# Analog.net
KiCad netlist of a schematic drawn in Altium Designer
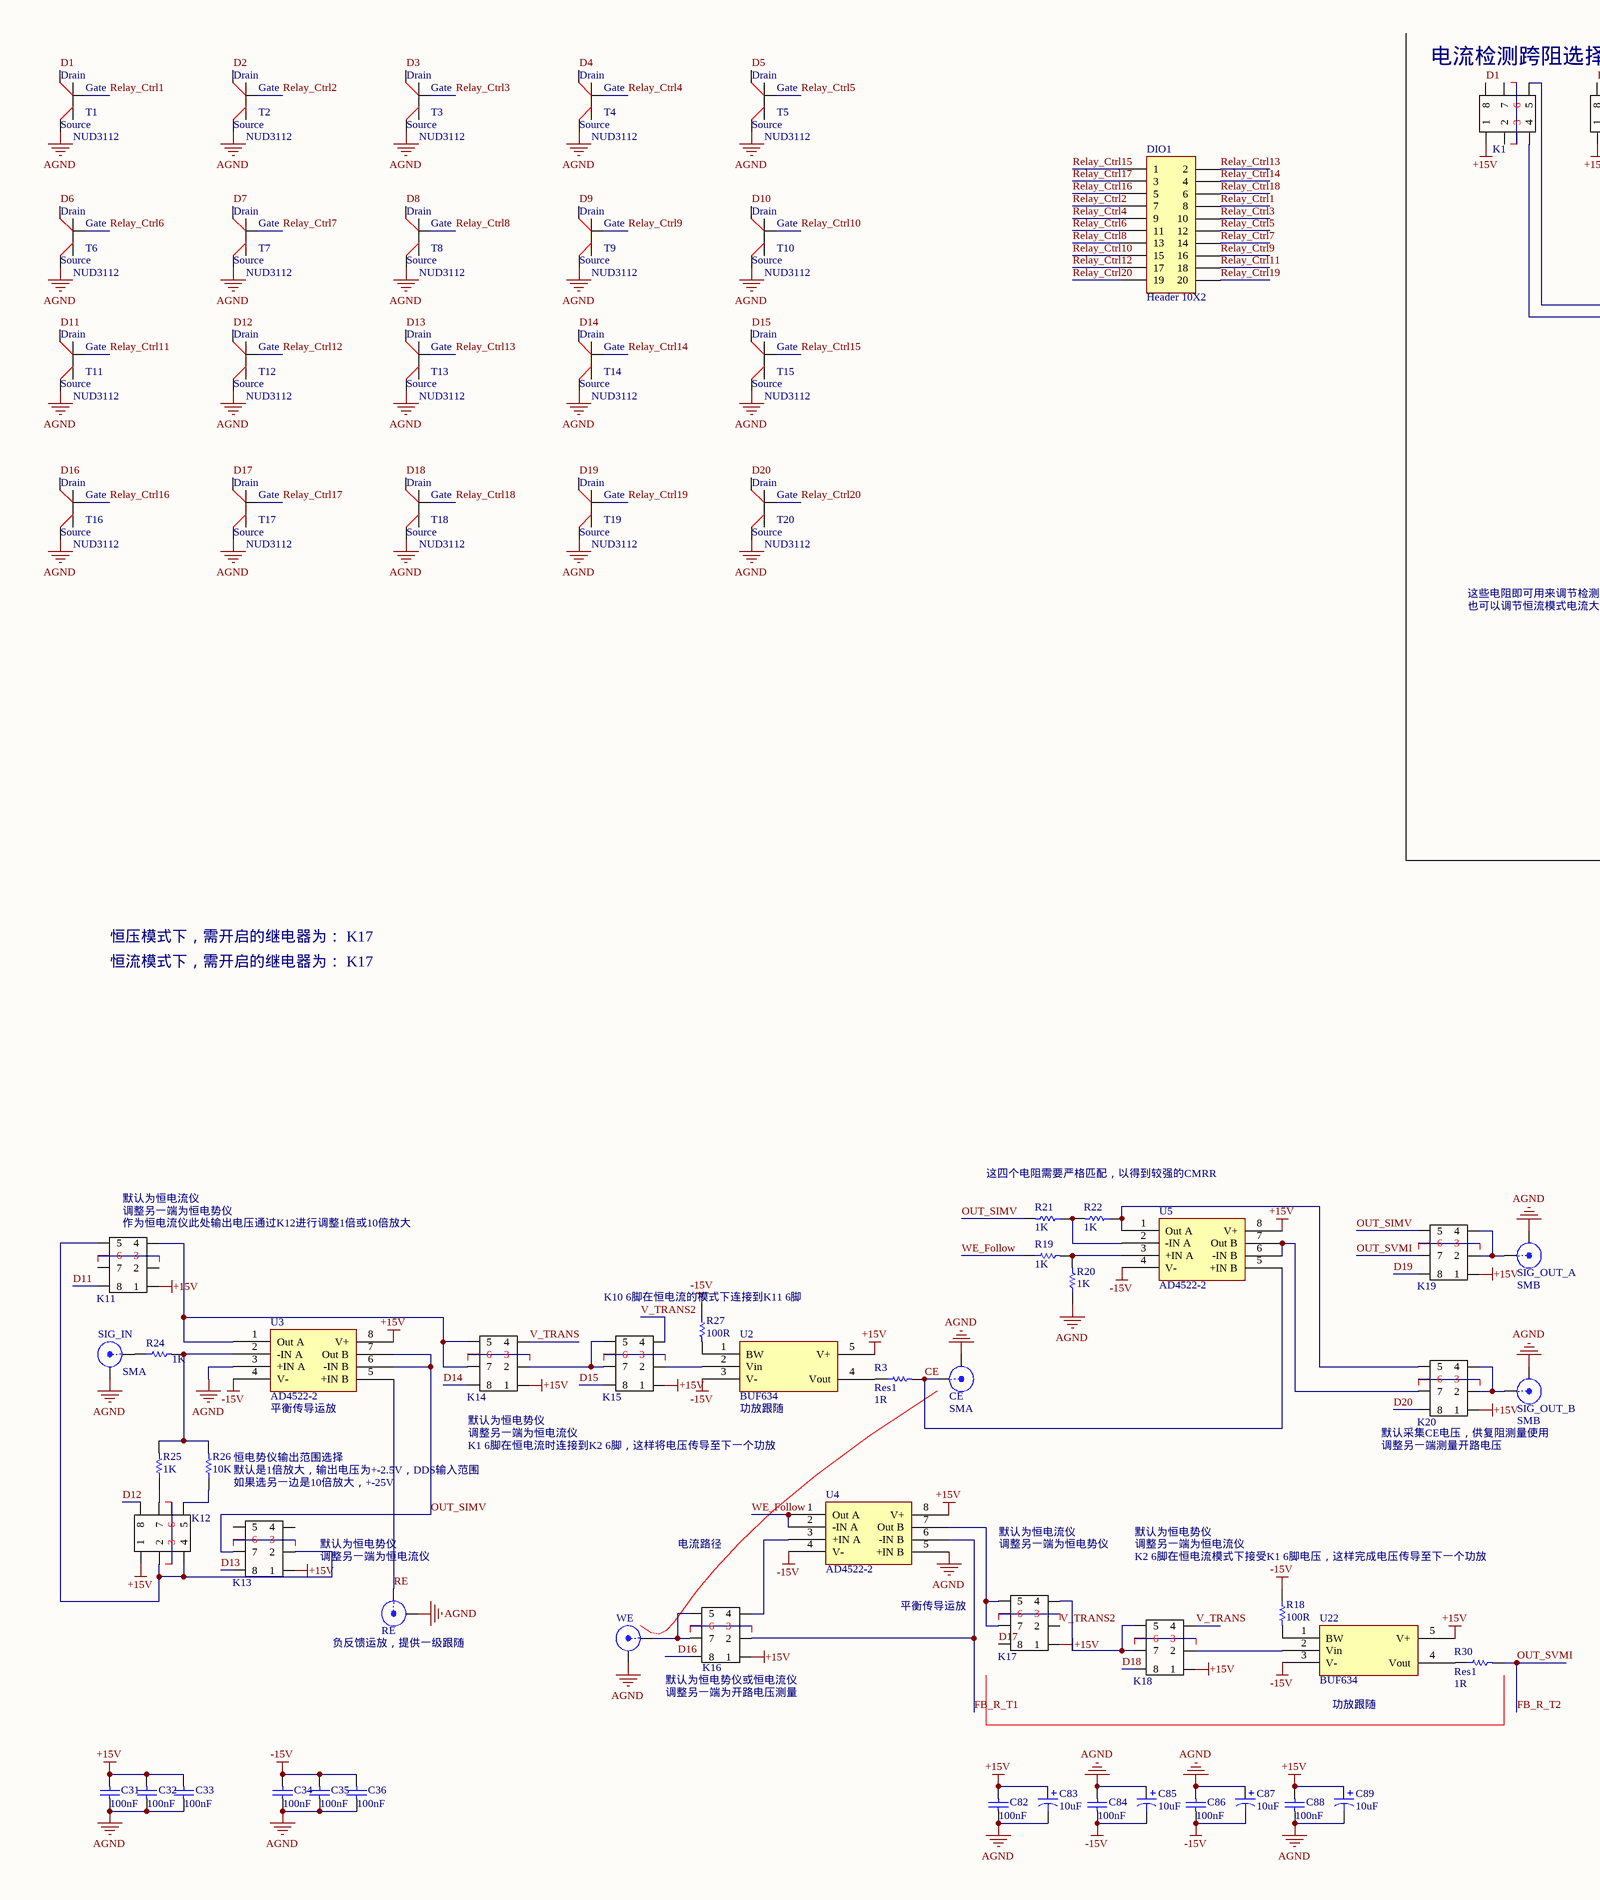
[diagram p0: Analog.SchDoc, left]
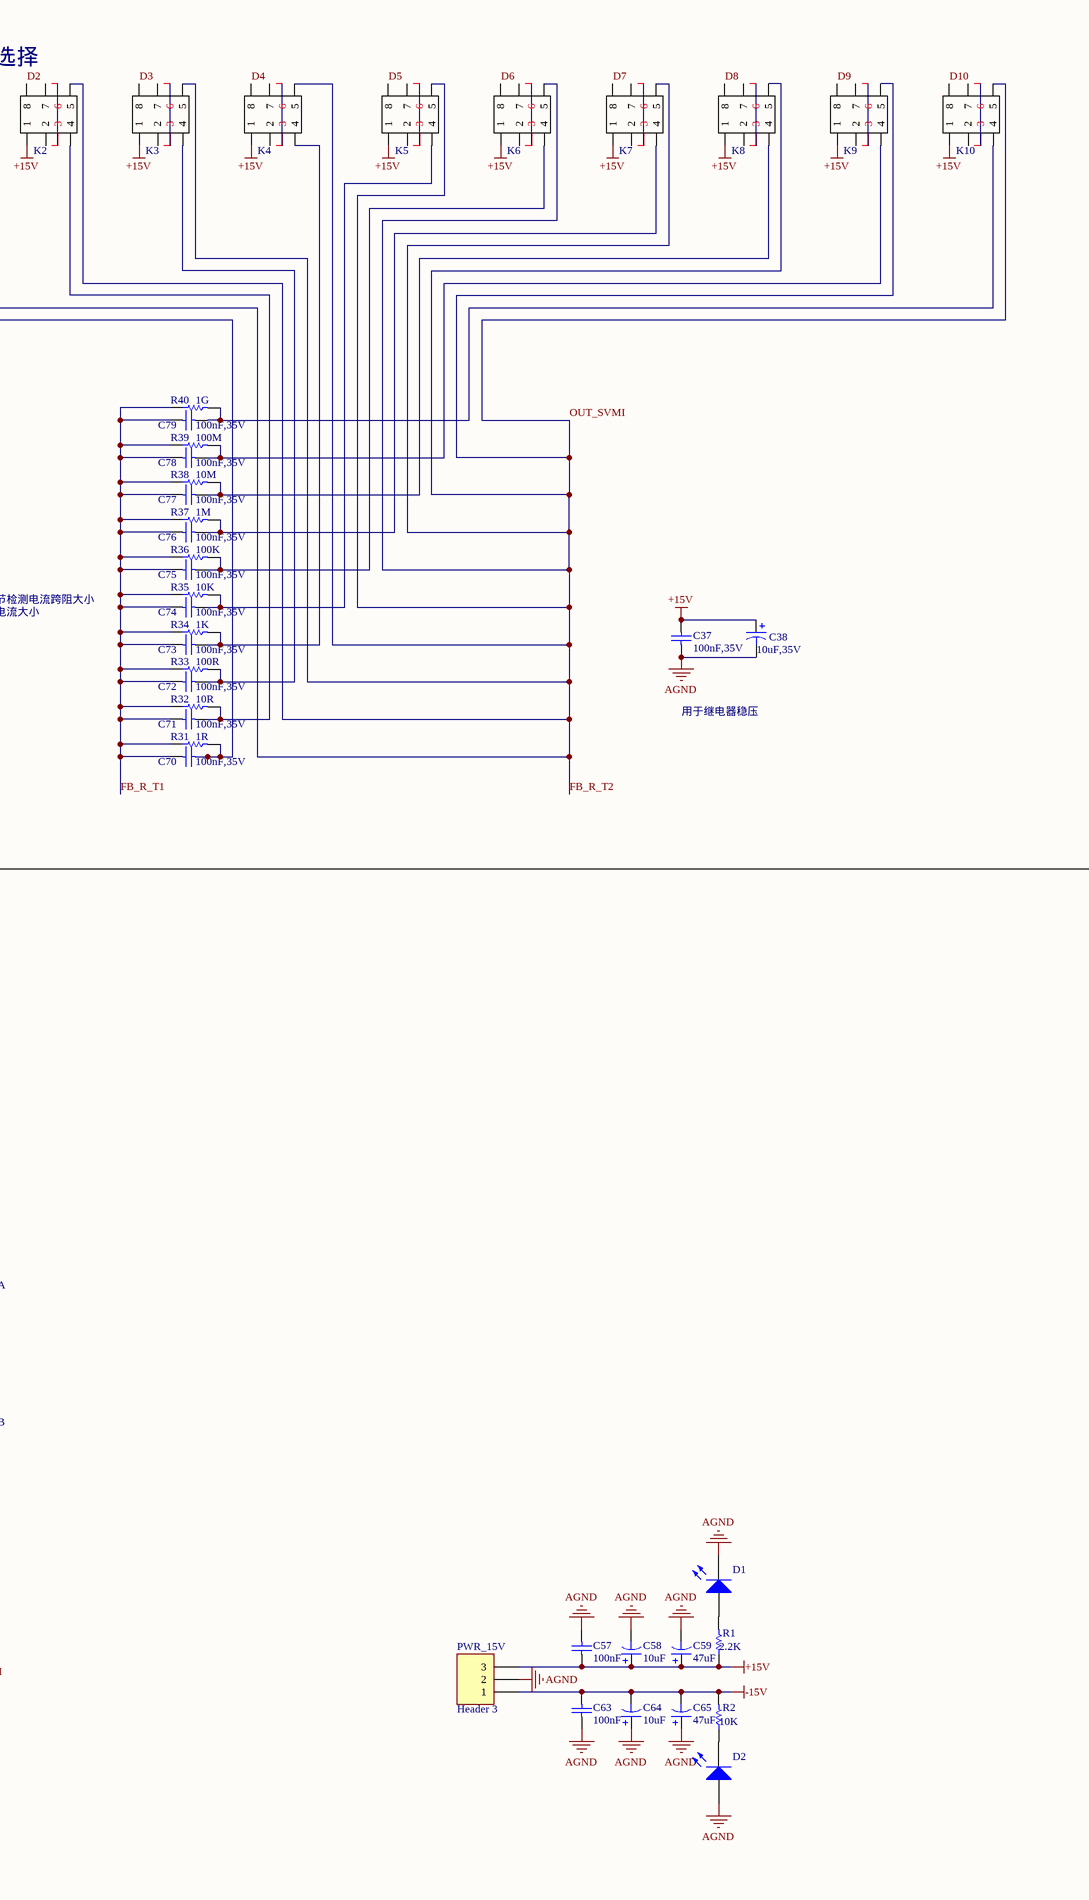
[diagram p1: Analog.SchDoc, right]

(export (version "E")
  (design (tool "Eeschema 10.0.6"))
  (components
    (comp (ref "C31")
      (value "100nF")
      (footprint "0805")
      (description "Capacitor")
      (fields (field (name "PUBLISHER") "Altium Limited"))
      (libsource (lib "Miscellaneous Devices") (part "Cap"))
    )
    (comp (ref "C32")
      (value "100nF")
      (footprint "0805")
      (description "Capacitor")
      (fields (field (name "PUBLISHER") "Altium Limited"))
      (libsource (lib "Miscellaneous Devices") (part "Cap"))
    )
    (comp (ref "C33")
      (value "100nF")
      (footprint "0805")
      (description "Capacitor")
      (fields (field (name "PUBLISHER") "Altium Limited"))
      (libsource (lib "Miscellaneous Devices") (part "Cap"))
    )
    (comp (ref "C34")
      (value "100nF")
      (footprint "0805")
      (description "Capacitor")
      (fields (field (name "PUBLISHER") "Altium Limited"))
      (libsource (lib "Miscellaneous Devices") (part "Cap"))
    )
    (comp (ref "C35")
      (value "100nF")
      (footprint "0805")
      (description "Capacitor")
      (fields (field (name "PUBLISHER") "Altium Limited"))
      (libsource (lib "Miscellaneous Devices") (part "Cap"))
    )
    (comp (ref "C36")
      (value "100nF")
      (footprint "0805")
      (description "Capacitor")
      (fields (field (name "PUBLISHER") "Altium Limited"))
      (libsource (lib "Miscellaneous Devices") (part "Cap"))
    )
    (comp (ref "C37")
      (value "100nF,35V")
      (footprint "0805")
      (description "Capacitor")
      (fields (field (name "Comment") "Cap") (field (name "PUBLISHER") "Altium Limited"))
      (libsource (lib "Miscellaneous Devices") (part "Cap"))
    )
    (comp (ref "C38")
      (value "10uF,35V")
      (footprint "6032_pol")
      (description "Polarized Capacitor (Radial)")
      (fields (field (name "Comment") "Cap Pol1") (field (name "PUBLISHER") "Altium Limited"))
      (libsource (lib "Miscellaneous Devices") (part "Cap Pol1"))
    )
    (comp (ref "C57")
      (value "100nF")
      (footprint "0805")
      (description "Capacitor,100V")
      (fields (field (name "PUBLISHER") "Altium Limited"))
      (libsource (lib "Miscellaneous Devices") (part "Cap"))
    )
    (comp (ref "C58")
      (value "10uF")
      (footprint "6032_pol")
      (description "Polarized Capacitor (Radial)")
      (fields (field (name "Comment") "10uF,50V") (field (name "PUBLISHER") "Altium Limited"))
      (libsource (lib "Miscellaneous Devices") (part "Cap Pol1"))
    )
    (comp (ref "C59")
      (value "47uF")
      (footprint "cap_pol_8*10.2")
      (description "Polarized Capacitor (Radial)")
      (fields (field (name "Comment") "47uF,50V") (field (name "PUBLISHER") "Altium Limited"))
      (libsource (lib "Miscellaneous Devices") (part "Cap Pol1"))
    )
    (comp (ref "C63")
      (value "100nF")
      (footprint "0805")
      (description "Capacitor,100V")
      (fields (field (name "PUBLISHER") "Altium Limited"))
      (libsource (lib "Miscellaneous Devices") (part "Cap"))
    )
    (comp (ref "C64")
      (value "10uF")
      (footprint "6032_pol")
      (description "Polarized Capacitor (Radial)")
      (fields (field (name "Comment") "10uF,50V") (field (name "PUBLISHER") "Altium Limited"))
      (libsource (lib "Miscellaneous Devices") (part "Cap Pol1"))
    )
    (comp (ref "C65")
      (value "47uF")
      (footprint "cap_pol_8*10.2")
      (description "Polarized Capacitor (Radial)")
      (fields (field (name "Comment") "47uF,50V") (field (name "PUBLISHER") "Altium Limited"))
      (libsource (lib "Miscellaneous Devices") (part "Cap Pol1"))
    )
    (comp (ref "C70")
      (value "100nF,35V")
      (footprint "0805")
      (description "Capacitor")
      (fields (field (name "Comment") "Cap") (field (name "PUBLISHER") "Altium Limited"))
      (libsource (lib "Miscellaneous Devices") (part "Cap"))
    )
    (comp (ref "C71")
      (value "100nF,35V")
      (footprint "0805")
      (description "Capacitor")
      (fields (field (name "Comment") "Cap") (field (name "PUBLISHER") "Altium Limited"))
      (libsource (lib "Miscellaneous Devices") (part "Cap"))
    )
    (comp (ref "C72")
      (value "100nF,35V")
      (footprint "0805")
      (description "Capacitor")
      (fields (field (name "Comment") "Cap") (field (name "PUBLISHER") "Altium Limited"))
      (libsource (lib "Miscellaneous Devices") (part "Cap"))
    )
    (comp (ref "C73")
      (value "100nF,35V")
      (footprint "0805")
      (description "Capacitor")
      (fields (field (name "Comment") "Cap") (field (name "PUBLISHER") "Altium Limited"))
      (libsource (lib "Miscellaneous Devices") (part "Cap"))
    )
    (comp (ref "C74")
      (value "100nF,35V")
      (footprint "0805")
      (description "Capacitor")
      (fields (field (name "Comment") "Cap") (field (name "PUBLISHER") "Altium Limited"))
      (libsource (lib "Miscellaneous Devices") (part "Cap"))
    )
    (comp (ref "C75")
      (value "100nF,35V")
      (footprint "0805")
      (description "Capacitor")
      (fields (field (name "Comment") "Cap") (field (name "PUBLISHER") "Altium Limited"))
      (libsource (lib "Miscellaneous Devices") (part "Cap"))
    )
    (comp (ref "C76")
      (value "100nF,35V")
      (footprint "0805")
      (description "Capacitor")
      (fields (field (name "Comment") "Cap") (field (name "PUBLISHER") "Altium Limited"))
      (libsource (lib "Miscellaneous Devices") (part "Cap"))
    )
    (comp (ref "C77")
      (value "100nF,35V")
      (footprint "0805")
      (description "Capacitor")
      (fields (field (name "Comment") "Cap") (field (name "PUBLISHER") "Altium Limited"))
      (libsource (lib "Miscellaneous Devices") (part "Cap"))
    )
    (comp (ref "C78")
      (value "100nF,35V")
      (footprint "0805")
      (description "Capacitor")
      (fields (field (name "Comment") "Cap") (field (name "PUBLISHER") "Altium Limited"))
      (libsource (lib "Miscellaneous Devices") (part "Cap"))
    )
    (comp (ref "C79")
      (value "100nF,35V")
      (footprint "0805")
      (description "Capacitor")
      (fields (field (name "Comment") "Cap") (field (name "PUBLISHER") "Altium Limited"))
      (libsource (lib "Miscellaneous Devices") (part "Cap"))
    )
    (comp (ref "C82")
      (value "100nF")
      (footprint "0805")
      (description "Capacitor")
      (fields (field (name "PUBLISHER") "Altium Limited"))
      (libsource (lib "Miscellaneous Devices") (part "Cap"))
    )
    (comp (ref "C83")
      (value "10uF")
      (footprint "6032_pol")
      (description "Polarized Capacitor (Radial)")
      (fields (field (name "PUBLISHER") "Altium Limited"))
      (libsource (lib "Miscellaneous Devices") (part "Cap Pol1"))
    )
    (comp (ref "C84")
      (value "100nF")
      (footprint "0805")
      (description "Capacitor")
      (fields (field (name "PUBLISHER") "Altium Limited"))
      (libsource (lib "Miscellaneous Devices") (part "Cap"))
    )
    (comp (ref "C85")
      (value "10uF")
      (footprint "6032_pol")
      (description "Polarized Capacitor (Radial)")
      (fields (field (name "PUBLISHER") "Altium Limited"))
      (libsource (lib "Miscellaneous Devices") (part "Cap Pol1"))
    )
    (comp (ref "C86")
      (value "100nF")
      (footprint "0805")
      (description "Capacitor")
      (fields (field (name "PUBLISHER") "Altium Limited"))
      (libsource (lib "Miscellaneous Devices") (part "Cap"))
    )
    (comp (ref "C87")
      (value "10uF")
      (footprint "6032_pol")
      (description "Polarized Capacitor (Radial)")
      (fields (field (name "PUBLISHER") "Altium Limited"))
      (libsource (lib "Miscellaneous Devices") (part "Cap Pol1"))
    )
    (comp (ref "C88")
      (value "100nF")
      (footprint "0805")
      (description "Capacitor")
      (fields (field (name "PUBLISHER") "Altium Limited"))
      (libsource (lib "Miscellaneous Devices") (part "Cap"))
    )
    (comp (ref "C89")
      (value "10uF")
      (footprint "6032_pol")
      (description "Polarized Capacitor (Radial)")
      (fields (field (name "PUBLISHER") "Altium Limited"))
      (libsource (lib "Miscellaneous Devices") (part "Cap Pol1"))
    )
    (comp (ref "CE")
      (value "SMA")
      (footprint "SMA_SMT")
      (description "SMB Straight Connector")
      (fields (field (name "PUBLISHER") "Altium Limited"))
      (libsource (lib "Miscellaneous Connectors") (part "SMB"))
    )
    (comp (ref "D1")
      (value "LED3")
      (footprint "0805_pol1")
      (description "Typical BLUE SiC LED")
      (fields (field (name "PUBLISHER") "Altium Limited"))
      (libsource (lib "Miscellaneous Devices") (part "LED3"))
    )
    (comp (ref "D2")
      (value "LED3")
      (footprint "0805_pol1")
      (description "Typical BLUE SiC LED")
      (fields (field (name "PUBLISHER") "Altium Limited"))
      (libsource (lib "Miscellaneous Devices") (part "LED3"))
    )
    (comp (ref "DIO1")
      (value "Header 10X2")
      (footprint "HDR2X10")
      (description "Header, 10-Pin, Dual row")
      (fields (field (name "PUBLISHER") "Altium Limited"))
      (libsource (lib "Miscellaneous Connectors") (part "Header 10X2"))
    )
    (comp (ref "K1")
      (value "AXICOM IM")
      (footprint "AXICOM_IM06")
      (libsource (lib "BinFeng_IC") (part "AXiCOM IM05"))
    )
    (comp (ref "K2")
      (value "AXICOM IM")
      (footprint "AXICOM_IM06")
      (libsource (lib "BinFeng_IC") (part "AXiCOM IM05"))
    )
    (comp (ref "K3")
      (value "AXICOM IM")
      (footprint "AXICOM_IM06")
      (libsource (lib "BinFeng_IC") (part "AXiCOM IM05"))
    )
    (comp (ref "K4")
      (value "AXICOM IM")
      (footprint "AXICOM_IM06")
      (libsource (lib "BinFeng_IC") (part "AXiCOM IM05"))
    )
    (comp (ref "K5")
      (value "AXICOM IM")
      (footprint "AXICOM_IM06")
      (libsource (lib "BinFeng_IC") (part "AXiCOM IM05"))
    )
    (comp (ref "K6")
      (value "AXICOM IM")
      (footprint "AXICOM_IM06")
      (libsource (lib "BinFeng_IC") (part "AXiCOM IM05"))
    )
    (comp (ref "K7")
      (value "AXICOM IM")
      (footprint "AXICOM_IM06")
      (libsource (lib "BinFeng_IC") (part "AXiCOM IM05"))
    )
    (comp (ref "K8")
      (value "AXICOM IM")
      (footprint "AXICOM_IM06")
      (libsource (lib "BinFeng_IC") (part "AXiCOM IM05"))
    )
    (comp (ref "K9")
      (value "AXICOM IM")
      (footprint "AXICOM_IM06")
      (libsource (lib "BinFeng_IC") (part "AXiCOM IM05"))
    )
    (comp (ref "K10")
      (value "AXICOM IM")
      (footprint "AXICOM_IM06")
      (libsource (lib "BinFeng_IC") (part "AXiCOM IM05"))
    )
    (comp (ref "K11")
      (value "AXICOM IM")
      (footprint "AXICOM_IM06")
      (libsource (lib "BinFeng_IC") (part "AXiCOM IM05"))
    )
    (comp (ref "K12")
      (value "AXICOM IM")
      (footprint "AXICOM_IM06")
      (libsource (lib "BinFeng_IC") (part "AXiCOM IM05"))
    )
    (comp (ref "K13")
      (value "AXICOM IM")
      (footprint "AXICOM_IM06")
      (libsource (lib "BinFeng_IC") (part "AXiCOM IM05"))
    )
    (comp (ref "K14")
      (value "AXICOM IM")
      (footprint "AXICOM_IM06")
      (libsource (lib "BinFeng_IC") (part "AXiCOM IM05"))
    )
    (comp (ref "K15")
      (value "AXICOM IM")
      (footprint "AXICOM_IM06")
      (libsource (lib "BinFeng_IC") (part "AXiCOM IM05"))
    )
    (comp (ref "K16")
      (value "AXICOM IM")
      (footprint "AXICOM_IM06")
      (libsource (lib "BinFeng_IC") (part "AXiCOM IM05"))
    )
    (comp (ref "K17")
      (value "AXICOM IM")
      (footprint "AXICOM_IM06")
      (libsource (lib "BinFeng_IC") (part "AXiCOM IM05"))
    )
    (comp (ref "K18")
      (value "AXICOM IM")
      (footprint "AXICOM_IM06")
      (libsource (lib "BinFeng_IC") (part "AXiCOM IM05"))
    )
    (comp (ref "K19")
      (value "AXICOM IM")
      (footprint "AXICOM_IM06")
      (libsource (lib "BinFeng_IC") (part "AXiCOM IM05"))
    )
    (comp (ref "K20")
      (value "AXICOM IM")
      (footprint "AXICOM_IM06")
      (libsource (lib "BinFeng_IC") (part "AXiCOM IM05"))
    )
    (comp (ref "PWR_15V")
      (value "Header 3")
      (footprint "PWR_3T")
      (description "Header, 3-Pin")
      (fields (field (name "PUBLISHER") "Altium Limited"))
      (libsource (lib "Miscellaneous Connectors") (part "Header 3"))
    )
    (comp (ref "R1")
      (value "2.2K")
      (footprint "BinFeng:0603")
      (description "Resistor")
      (fields (field (name "Comment") "10K") (field (name "PUBLISHER") "Altium Limited"))
      (libsource (lib "Miscellaneous Devices") (part "Res1"))
    )
    (comp (ref "R2")
      (value "10K")
      (footprint "BinFeng:0603")
      (description "Resistor")
      (fields (field (name "Comment") "2.2K") (field (name "PUBLISHER") "Altium Limited"))
      (libsource (lib "Miscellaneous Devices") (part "Res1"))
    )
    (comp (ref "R3")
      (value "Res1")
      (footprint "1206")
      (description "Resistor")
      (fields (field (name "ALTIUM_VALUE") "1R") (field (name "PUBLISHER") "Altium Limited"))
      (libsource (lib "Miscellaneous Devices") (part "Res1"))
    )
    (comp (ref "R18")
      (value "100R")
      (footprint "0805")
      (description "Resistor")
      (fields (field (name "Comment") "Res1") (field (name "PUBLISHER") "Altium Limited"))
      (libsource (lib "Miscellaneous Devices") (part "Res1"))
    )
    (comp (ref "R19")
      (value "1K")
      (footprint "0805")
      (description "Resistor")
      (fields (field (name "Comment") "Res1") (field (name "PUBLISHER") "Altium Limited"))
      (libsource (lib "Miscellaneous Devices") (part "Res1"))
    )
    (comp (ref "R20")
      (value "1K")
      (footprint "0805")
      (description "Resistor")
      (fields (field (name "Comment") "Res1") (field (name "PUBLISHER") "Altium Limited"))
      (libsource (lib "Miscellaneous Devices") (part "Res1"))
    )
    (comp (ref "R21")
      (value "1K")
      (footprint "0805")
      (description "Resistor")
      (fields (field (name "Comment") "Res1") (field (name "PUBLISHER") "Altium Limited"))
      (libsource (lib "Miscellaneous Devices") (part "Res1"))
    )
    (comp (ref "R22")
      (value "1K")
      (footprint "0805")
      (description "Resistor")
      (fields (field (name "Comment") "Res1") (field (name "PUBLISHER") "Altium Limited"))
      (libsource (lib "Miscellaneous Devices") (part "Res1"))
    )
    (comp (ref "R24")
      (value "1K")
      (footprint "0805")
      (description "Resistor")
      (fields (field (name "Comment") "Res1") (field (name "PUBLISHER") "Altium Limited"))
      (libsource (lib "Miscellaneous Devices") (part "Res1"))
    )
    (comp (ref "R25")
      (value "1K")
      (footprint "0805")
      (description "Resistor")
      (fields (field (name "Comment") "Res1") (field (name "PUBLISHER") "Altium Limited"))
      (libsource (lib "Miscellaneous Devices") (part "Res1"))
    )
    (comp (ref "R26")
      (value "10K")
      (footprint "0805")
      (description "Resistor")
      (fields (field (name "Comment") "Res1") (field (name "PUBLISHER") "Altium Limited"))
      (libsource (lib "Miscellaneous Devices") (part "Res1"))
    )
    (comp (ref "R27")
      (value "100R")
      (footprint "0805")
      (description "Resistor")
      (fields (field (name "Comment") "Res1") (field (name "PUBLISHER") "Altium Limited"))
      (libsource (lib "Miscellaneous Devices") (part "Res1"))
    )
    (comp (ref "R30")
      (value "Res1")
      (footprint "1206")
      (description "Resistor")
      (fields (field (name "ALTIUM_VALUE") "1R") (field (name "PUBLISHER") "Altium Limited"))
      (libsource (lib "Miscellaneous Devices") (part "Res1"))
    )
    (comp (ref "R31")
      (value "1R")
      (footprint "0805")
      (description "Resistor")
      (fields (field (name "Comment") "Res1") (field (name "PUBLISHER") "Altium Limited"))
      (libsource (lib "Miscellaneous Devices") (part "Res1"))
    )
    (comp (ref "R32")
      (value "10R")
      (footprint "0805")
      (description "Resistor")
      (fields (field (name "Comment") "Res1") (field (name "PUBLISHER") "Altium Limited"))
      (libsource (lib "Miscellaneous Devices") (part "Res1"))
    )
    (comp (ref "R33")
      (value "100R")
      (footprint "0805")
      (description "Resistor")
      (fields (field (name "Comment") "Res1") (field (name "PUBLISHER") "Altium Limited"))
      (libsource (lib "Miscellaneous Devices") (part "Res1"))
    )
    (comp (ref "R34")
      (value "1K")
      (footprint "0805")
      (description "Resistor")
      (fields (field (name "Comment") "Res1") (field (name "PUBLISHER") "Altium Limited"))
      (libsource (lib "Miscellaneous Devices") (part "Res1"))
    )
    (comp (ref "R35")
      (value "10K")
      (footprint "0805")
      (description "Resistor")
      (fields (field (name "Comment") "Res1") (field (name "PUBLISHER") "Altium Limited"))
      (libsource (lib "Miscellaneous Devices") (part "Res1"))
    )
    (comp (ref "R36")
      (value "100K")
      (footprint "0805")
      (description "Resistor")
      (fields (field (name "Comment") "Res1") (field (name "PUBLISHER") "Altium Limited"))
      (libsource (lib "Miscellaneous Devices") (part "Res1"))
    )
    (comp (ref "R37")
      (value "1M")
      (footprint "0805")
      (description "Resistor")
      (fields (field (name "Comment") "Res1") (field (name "PUBLISHER") "Altium Limited"))
      (libsource (lib "Miscellaneous Devices") (part "Res1"))
    )
    (comp (ref "R38")
      (value "10M")
      (footprint "0805")
      (description "Resistor")
      (fields (field (name "Comment") "Res1") (field (name "PUBLISHER") "Altium Limited"))
      (libsource (lib "Miscellaneous Devices") (part "Res1"))
    )
    (comp (ref "R39")
      (value "100M")
      (footprint "0805")
      (description "Resistor")
      (fields (field (name "Comment") "Res1") (field (name "PUBLISHER") "Altium Limited"))
      (libsource (lib "Miscellaneous Devices") (part "Res1"))
    )
    (comp (ref "R40")
      (value "1G")
      (footprint "0805")
      (description "Resistor")
      (fields (field (name "Comment") "Res1") (field (name "PUBLISHER") "Altium Limited"))
      (libsource (lib "Miscellaneous Devices") (part "Res1"))
    )
    (comp (ref "RE")
      (value "SMB")
      (footprint "SMA_SMT")
      (description "SMB Straight Connector")
      (fields (field (name "PUBLISHER") "Altium Limited"))
      (libsource (lib "Miscellaneous Connectors") (part "SMB"))
    )
    (comp (ref "SIG_IN")
      (value "SMA")
      (footprint "SMA_SMT")
      (description "SMB Straight Connector")
      (fields (field (name "PUBLISHER") "Altium Limited"))
      (libsource (lib "Miscellaneous Connectors") (part "SMB"))
    )
    (comp (ref "SIG_OUT_A")
      (value "SMB")
      (footprint "SMA_SMT")
      (description "SMB Straight Connector")
      (fields (field (name "PUBLISHER") "Altium Limited"))
      (libsource (lib "Miscellaneous Connectors") (part "SMB"))
    )
    (comp (ref "SIG_OUT_B")
      (value "SMB")
      (footprint "SMA_SMT")
      (description "SMB Straight Connector")
      (fields (field (name "PUBLISHER") "Altium Limited"))
      (libsource (lib "Miscellaneous Connectors") (part "SMB"))
    )
    (comp (ref "T1")
      (value "NUD3112")
      (footprint "SOT-23")
      (description "Relay Driver 5V Supply")
      (libsource (lib "BinFeng_IC") (part "NUD3105"))
    )
    (comp (ref "T2")
      (value "NUD3112")
      (footprint "SOT-23")
      (description "Relay Driver 5V Supply")
      (libsource (lib "BinFeng_IC") (part "NUD3105"))
    )
    (comp (ref "T3")
      (value "NUD3112")
      (footprint "SOT-23")
      (description "Relay Driver 5V Supply")
      (libsource (lib "BinFeng_IC") (part "NUD3105"))
    )
    (comp (ref "T4")
      (value "NUD3112")
      (footprint "SOT-23")
      (description "Relay Driver 5V Supply")
      (libsource (lib "BinFeng_IC") (part "NUD3105"))
    )
    (comp (ref "T5")
      (value "NUD3112")
      (footprint "SOT-23")
      (description "Relay Driver 5V Supply")
      (libsource (lib "BinFeng_IC") (part "NUD3105"))
    )
    (comp (ref "T6")
      (value "NUD3112")
      (footprint "SOT-23")
      (description "Relay Driver 5V Supply")
      (libsource (lib "BinFeng_IC") (part "NUD3105"))
    )
    (comp (ref "T7")
      (value "NUD3112")
      (footprint "SOT-23")
      (description "Relay Driver 5V Supply")
      (libsource (lib "BinFeng_IC") (part "NUD3105"))
    )
    (comp (ref "T8")
      (value "NUD3112")
      (footprint "SOT-23")
      (description "Relay Driver 5V Supply")
      (libsource (lib "BinFeng_IC") (part "NUD3105"))
    )
    (comp (ref "T9")
      (value "NUD3112")
      (footprint "SOT-23")
      (description "Relay Driver 5V Supply")
      (libsource (lib "BinFeng_IC") (part "NUD3105"))
    )
    (comp (ref "T10")
      (value "NUD3112")
      (footprint "SOT-23")
      (description "Relay Driver 5V Supply")
      (libsource (lib "BinFeng_IC") (part "NUD3105"))
    )
    (comp (ref "T11")
      (value "NUD3112")
      (footprint "SOT-23")
      (description "Relay Driver 5V Supply")
      (libsource (lib "BinFeng_IC") (part "NUD3105"))
    )
    (comp (ref "T12")
      (value "NUD3112")
      (footprint "SOT-23")
      (description "Relay Driver 5V Supply")
      (libsource (lib "BinFeng_IC") (part "NUD3105"))
    )
    (comp (ref "T13")
      (value "NUD3112")
      (footprint "SOT-23")
      (description "Relay Driver 5V Supply")
      (libsource (lib "BinFeng_IC") (part "NUD3105"))
    )
    (comp (ref "T14")
      (value "NUD3112")
      (footprint "SOT-23")
      (description "Relay Driver 5V Supply")
      (libsource (lib "BinFeng_IC") (part "NUD3105"))
    )
    (comp (ref "T15")
      (value "NUD3112")
      (footprint "SOT-23")
      (description "Relay Driver 5V Supply")
      (libsource (lib "BinFeng_IC") (part "NUD3105"))
    )
    (comp (ref "T16")
      (value "NUD3112")
      (footprint "SOT-23")
      (description "Relay Driver 5V Supply")
      (libsource (lib "BinFeng_IC") (part "NUD3105"))
    )
    (comp (ref "T17")
      (value "NUD3112")
      (footprint "SOT-23")
      (description "Relay Driver 5V Supply")
      (libsource (lib "BinFeng_IC") (part "NUD3105"))
    )
    (comp (ref "T18")
      (value "NUD3112")
      (footprint "SOT-23")
      (description "Relay Driver 5V Supply")
      (libsource (lib "BinFeng_IC") (part "NUD3105"))
    )
    (comp (ref "T19")
      (value "NUD3112")
      (footprint "SOT-23")
      (description "Relay Driver 5V Supply")
      (libsource (lib "BinFeng_IC") (part "NUD3105"))
    )
    (comp (ref "T20")
      (value "NUD3112")
      (footprint "SOT-23")
      (description "Relay Driver 5V Supply")
      (libsource (lib "BinFeng_IC") (part "NUD3105"))
    )
    (comp (ref "U2") (value "BUF634") (footprint "PSFM-T5") (libsource (lib "BinFeng_IC") (part "BUF634")))
    (comp (ref "U3") (value "AD4522-2") (footprint "SO-8N") (libsource (lib "BinFeng_IC") (part "AD8676")))
    (comp (ref "U4") (value "AD4522-2") (footprint "SO-8N") (libsource (lib "BinFeng_IC") (part "AD8676")))
    (comp (ref "U5") (value "AD4522-2") (footprint "SO-8N") (libsource (lib "BinFeng_IC") (part "AD8676")))
    (comp (ref "U22") (value "BUF634") (footprint "PSFM-T5") (libsource (lib "BinFeng_IC") (part "BUF634")))
    (comp (ref "WE")
      (value "SMB")
      (footprint "SMA_SMT")
      (description "SMB Straight Connector")
      (fields (field (name "PUBLISHER") "Altium Limited"))
      (libsource (lib "Miscellaneous Connectors") (part "SMB"))
    )
  )
  (nets
    (net (code "1") (name "+15V") (class "Default")
      (node (ref "C31") (pin "2") (pinfunction "2_2") (pintype "passive"))
      (node (ref "C32") (pin "2") (pinfunction "2_2") (pintype "passive"))
      (node (ref "C33") (pin "2") (pinfunction "2_2") (pintype "passive"))
      (node (ref "C37") (pin "2") (pinfunction "2_2") (pintype "passive"))
      (node (ref "C38") (pin "1") (pinfunction "1_1") (pintype "passive"))
      (node (ref "C57") (pin "2") (pinfunction "2_2") (pintype "passive"))
      (node (ref "C58") (pin "1") (pinfunction "1_1") (pintype "passive"))
      (node (ref "C59") (pin "1") (pinfunction "1_1") (pintype "passive"))
      (node (ref "C82") (pin "2") (pinfunction "2_2") (pintype "passive"))
      (node (ref "C83") (pin "1") (pinfunction "1_1") (pintype "passive"))
      (node (ref "C88") (pin "2") (pinfunction "2_2") (pintype "passive"))
      (node (ref "C89") (pin "1") (pinfunction "1_1") (pintype "passive"))
      (node (ref "K1") (pin "1") (pinfunction "1_1") (pintype "passive"))
      (node (ref "K10") (pin "1") (pinfunction "1_1") (pintype "passive"))
      (node (ref "K11") (pin "1") (pinfunction "1_1") (pintype "passive"))
      (node (ref "K12") (pin "1") (pinfunction "1_1") (pintype "passive"))
      (node (ref "K13") (pin "1") (pinfunction "1_1") (pintype "passive"))
      (node (ref "K14") (pin "1") (pinfunction "1_1") (pintype "passive"))
      (node (ref "K15") (pin "1") (pinfunction "1_1") (pintype "passive"))
      (node (ref "K16") (pin "1") (pinfunction "1_1") (pintype "passive"))
      (node (ref "K17") (pin "1") (pinfunction "1_1") (pintype "passive"))
      (node (ref "K18") (pin "1") (pinfunction "1_1") (pintype "passive"))
      (node (ref "K19") (pin "1") (pinfunction "1_1") (pintype "passive"))
      (node (ref "K2") (pin "1") (pinfunction "1_1") (pintype "passive"))
      (node (ref "K20") (pin "1") (pinfunction "1_1") (pintype "passive"))
      (node (ref "K3") (pin "1") (pinfunction "1_1") (pintype "passive"))
      (node (ref "K4") (pin "1") (pinfunction "1_1") (pintype "passive"))
      (node (ref "K5") (pin "1") (pinfunction "1_1") (pintype "passive"))
      (node (ref "K6") (pin "1") (pinfunction "1_1") (pintype "passive"))
      (node (ref "K7") (pin "1") (pinfunction "1_1") (pintype "passive"))
      (node (ref "K8") (pin "1") (pinfunction "1_1") (pintype "passive"))
      (node (ref "K9") (pin "1") (pinfunction "1_1") (pintype "passive"))
      (node (ref "PWR_15V") (pin "3") (pinfunction "3_3") (pintype "passive"))
      (node (ref "R1") (pin "1") (pinfunction "1_1") (pintype "passive"))
      (node (ref "U2") (pin "5") (pinfunction "V+_5") (pintype "passive"))
      (node (ref "U22") (pin "5") (pinfunction "V+_5") (pintype "passive"))
      (node (ref "U3") (pin "8") (pinfunction "V+_8") (pintype "passive"))
      (node (ref "U4") (pin "8") (pinfunction "V+_8") (pintype "passive"))
      (node (ref "U5") (pin "8") (pinfunction "V+_8") (pintype "passive"))
    )
    (net (code "2") (name "-15V") (class "Default")
      (node (ref "C34") (pin "2") (pinfunction "2_2") (pintype "passive"))
      (node (ref "C35") (pin "2") (pinfunction "2_2") (pintype "passive"))
      (node (ref "C36") (pin "2") (pinfunction "2_2") (pintype "passive"))
      (node (ref "C63") (pin "1") (pinfunction "1_1") (pintype "passive"))
      (node (ref "C64") (pin "2") (pinfunction "2_2") (pintype "passive"))
      (node (ref "C65") (pin "2") (pinfunction "2_2") (pintype "passive"))
      (node (ref "C84") (pin "1") (pinfunction "1_1") (pintype "passive"))
      (node (ref "C85") (pin "2") (pinfunction "2_2") (pintype "passive"))
      (node (ref "C86") (pin "1") (pinfunction "1_1") (pintype "passive"))
      (node (ref "C87") (pin "2") (pinfunction "2_2") (pintype "passive"))
      (node (ref "PWR_15V") (pin "1") (pinfunction "1_1") (pintype "passive"))
      (node (ref "R18") (pin "1") (pinfunction "1_1") (pintype "passive"))
      (node (ref "R2") (pin "2") (pinfunction "2_2") (pintype "passive"))
      (node (ref "R27") (pin "1") (pinfunction "1_1") (pintype "passive"))
      (node (ref "U2") (pin "3") (pinfunction "V-_3") (pintype "passive"))
      (node (ref "U22") (pin "3") (pinfunction "V-_3") (pintype "passive"))
      (node (ref "U3") (pin "4") (pinfunction "V-_4") (pintype "passive"))
      (node (ref "U4") (pin "4") (pinfunction "V-_4") (pintype "passive"))
      (node (ref "U5") (pin "4") (pinfunction "V-_4") (pintype "passive"))
    )
    (net (code "3") (name "/CE") (class "Default")
      (node (ref "CE") (pin "1") (pinfunction "X_1") (pintype "passive"))
      (node (ref "R3") (pin "2") (pinfunction "2_2") (pintype "passive"))
      (node (ref "U5") (pin "5") (pinfunction "+IN_B_5") (pintype "passive"))
    )
    (net (code "4") (name "/D1") (class "Default")
      (node (ref "K1") (pin "8") (pinfunction "8_8") (pintype "passive"))
      (node (ref "T1") (pin "3") (pinfunction "Drain_3") (pintype "passive"))
    )
    (net (code "5") (name "/D2") (class "Default")
      (node (ref "K2") (pin "8") (pinfunction "8_8") (pintype "passive"))
      (node (ref "T2") (pin "3") (pinfunction "Drain_3") (pintype "passive"))
    )
    (net (code "6") (name "/D3") (class "Default")
      (node (ref "K3") (pin "8") (pinfunction "8_8") (pintype "passive"))
      (node (ref "T3") (pin "3") (pinfunction "Drain_3") (pintype "passive"))
    )
    (net (code "7") (name "/D4") (class "Default")
      (node (ref "K4") (pin "8") (pinfunction "8_8") (pintype "passive"))
      (node (ref "T4") (pin "3") (pinfunction "Drain_3") (pintype "passive"))
    )
    (net (code "8") (name "/D5") (class "Default")
      (node (ref "K5") (pin "8") (pinfunction "8_8") (pintype "passive"))
      (node (ref "T5") (pin "3") (pinfunction "Drain_3") (pintype "passive"))
    )
    (net (code "9") (name "/D6") (class "Default")
      (node (ref "K6") (pin "8") (pinfunction "8_8") (pintype "passive"))
      (node (ref "T6") (pin "3") (pinfunction "Drain_3") (pintype "passive"))
    )
    (net (code "10") (name "/D7") (class "Default")
      (node (ref "K7") (pin "8") (pinfunction "8_8") (pintype "passive"))
      (node (ref "T7") (pin "3") (pinfunction "Drain_3") (pintype "passive"))
    )
    (net (code "11") (name "/D8") (class "Default")
      (node (ref "K8") (pin "8") (pinfunction "8_8") (pintype "passive"))
      (node (ref "T8") (pin "3") (pinfunction "Drain_3") (pintype "passive"))
    )
    (net (code "12") (name "/D9") (class "Default")
      (node (ref "K9") (pin "8") (pinfunction "8_8") (pintype "passive"))
      (node (ref "T9") (pin "3") (pinfunction "Drain_3") (pintype "passive"))
    )
    (net (code "13") (name "/D10") (class "Default")
      (node (ref "K10") (pin "8") (pinfunction "8_8") (pintype "passive"))
      (node (ref "T10") (pin "3") (pinfunction "Drain_3") (pintype "passive"))
    )
    (net (code "14") (name "/D11") (class "Default")
      (node (ref "K11") (pin "8") (pinfunction "8_8") (pintype "passive"))
      (node (ref "T11") (pin "3") (pinfunction "Drain_3") (pintype "passive"))
    )
    (net (code "15") (name "/D12") (class "Default")
      (node (ref "K12") (pin "8") (pinfunction "8_8") (pintype "passive"))
      (node (ref "T12") (pin "3") (pinfunction "Drain_3") (pintype "passive"))
    )
    (net (code "16") (name "/D13") (class "Default")
      (node (ref "K13") (pin "8") (pinfunction "8_8") (pintype "passive"))
      (node (ref "T13") (pin "3") (pinfunction "Drain_3") (pintype "passive"))
    )
    (net (code "17") (name "/D14") (class "Default")
      (node (ref "K14") (pin "8") (pinfunction "8_8") (pintype "passive"))
      (node (ref "T14") (pin "3") (pinfunction "Drain_3") (pintype "passive"))
    )
    (net (code "18") (name "/D15") (class "Default")
      (node (ref "K15") (pin "8") (pinfunction "8_8") (pintype "passive"))
      (node (ref "T15") (pin "3") (pinfunction "Drain_3") (pintype "passive"))
    )
    (net (code "19") (name "/D16") (class "Default")
      (node (ref "K16") (pin "8") (pinfunction "8_8") (pintype "passive"))
      (node (ref "T16") (pin "3") (pinfunction "Drain_3") (pintype "passive"))
    )
    (net (code "20") (name "/D17") (class "Default")
      (node (ref "K17") (pin "8") (pinfunction "8_8") (pintype "passive"))
      (node (ref "T17") (pin "3") (pinfunction "Drain_3") (pintype "passive"))
    )
    (net (code "21") (name "/D18") (class "Default")
      (node (ref "K18") (pin "8") (pinfunction "8_8") (pintype "passive"))
      (node (ref "T18") (pin "3") (pinfunction "Drain_3") (pintype "passive"))
    )
    (net (code "22") (name "/D19") (class "Default")
      (node (ref "K19") (pin "8") (pinfunction "8_8") (pintype "passive"))
      (node (ref "T19") (pin "3") (pinfunction "Drain_3") (pintype "passive"))
    )
    (net (code "23") (name "/D20") (class "Default")
      (node (ref "K20") (pin "8") (pinfunction "8_8") (pintype "passive"))
      (node (ref "T20") (pin "3") (pinfunction "Drain_3") (pintype "passive"))
    )
    (net (code "24") (name "/FB_R_T1") (class "Default")
      (node (ref "C70") (pin "1") (pinfunction "1_1") (pintype "passive"))
      (node (ref "C71") (pin "1") (pinfunction "1_1") (pintype "passive"))
      (node (ref "C72") (pin "1") (pinfunction "1_1") (pintype "passive"))
      (node (ref "C73") (pin "1") (pinfunction "1_1") (pintype "passive"))
      (node (ref "C74") (pin "1") (pinfunction "1_1") (pintype "passive"))
      (node (ref "C75") (pin "1") (pinfunction "1_1") (pintype "passive"))
      (node (ref "C76") (pin "1") (pinfunction "1_1") (pintype "passive"))
      (node (ref "C77") (pin "1") (pinfunction "1_1") (pintype "passive"))
      (node (ref "C78") (pin "1") (pinfunction "1_1") (pintype "passive"))
      (node (ref "C79") (pin "1") (pinfunction "1_1") (pintype "passive"))
      (node (ref "K16") (pin "2") (pinfunction "2_2") (pintype "passive"))
      (node (ref "R31") (pin "1") (pinfunction "1_1") (pintype "passive"))
      (node (ref "R32") (pin "1") (pinfunction "1_1") (pintype "passive"))
      (node (ref "R33") (pin "1") (pinfunction "1_1") (pintype "passive"))
      (node (ref "R34") (pin "1") (pinfunction "1_1") (pintype "passive"))
      (node (ref "R35") (pin "1") (pinfunction "1_1") (pintype "passive"))
      (node (ref "R36") (pin "1") (pinfunction "1_1") (pintype "passive"))
      (node (ref "R37") (pin "1") (pinfunction "1_1") (pintype "passive"))
      (node (ref "R38") (pin "1") (pinfunction "1_1") (pintype "passive"))
      (node (ref "R39") (pin "1") (pinfunction "1_1") (pintype "passive"))
      (node (ref "R40") (pin "1") (pinfunction "1_1") (pintype "passive"))
      (node (ref "U4") (pin "6") (pinfunction "-IN_B_6") (pintype "passive"))
    )
    (net (code "25") (name "/FB_R_T2") (class "Default")
      (node (ref "K1") (pin "5") (pinfunction "5_5") (pintype "passive"))
      (node (ref "K10") (pin "5") (pinfunction "5_5") (pintype "passive"))
      (node (ref "K19") (pin "7") (pinfunction "7_7") (pintype "passive"))
      (node (ref "K2") (pin "5") (pinfunction "5_5") (pintype "passive"))
      (node (ref "K3") (pin "5") (pinfunction "5_5") (pintype "passive"))
      (node (ref "K4") (pin "5") (pinfunction "5_5") (pintype "passive"))
      (node (ref "K5") (pin "5") (pinfunction "5_5") (pintype "passive"))
      (node (ref "K6") (pin "5") (pinfunction "5_5") (pintype "passive"))
      (node (ref "K7") (pin "5") (pinfunction "5_5") (pintype "passive"))
      (node (ref "K8") (pin "5") (pinfunction "5_5") (pintype "passive"))
      (node (ref "K9") (pin "5") (pinfunction "5_5") (pintype "passive"))
      (node (ref "R30") (pin "2") (pinfunction "2_2") (pintype "passive"))
    )
    (net (code "26") (name "/OUT_SIMV") (class "Default")
      (node (ref "K13") (pin "7") (pinfunction "7_7") (pintype "passive"))
      (node (ref "K19") (pin "5") (pinfunction "5_5") (pintype "passive"))
      (node (ref "R21") (pin "2") (pinfunction "2_2") (pintype "passive"))
      (node (ref "U3") (pin "6") (pinfunction "-IN_B_6") (pintype "passive"))
      (node (ref "U3") (pin "7") (pinfunction "Out_B_7") (pintype "passive"))
    )
    (net (code "27") (name "/RE") (class "Default")
      (node (ref "RE") (pin "1") (pinfunction "X_1") (pintype "passive"))
      (node (ref "U3") (pin "5") (pinfunction "+IN_B_5") (pintype "passive"))
    )
    (net (code "28") (name "/Relay_Ctrl1") (class "Default")
      (node (ref "DIO1") (pin "8") (pinfunction "8_8") (pintype "passive"))
      (node (ref "T1") (pin "1") (pinfunction "Gate_1") (pintype "passive"))
    )
    (net (code "29") (name "/Relay_Ctrl2") (class "Default")
      (node (ref "DIO1") (pin "7") (pinfunction "7_7") (pintype "passive"))
      (node (ref "T2") (pin "1") (pinfunction "Gate_1") (pintype "passive"))
    )
    (net (code "30") (name "/Relay_Ctrl3") (class "Default")
      (node (ref "DIO1") (pin "10") (pinfunction "10_10") (pintype "passive"))
      (node (ref "T3") (pin "1") (pinfunction "Gate_1") (pintype "passive"))
    )
    (net (code "31") (name "/Relay_Ctrl4") (class "Default")
      (node (ref "DIO1") (pin "9") (pinfunction "9_9") (pintype "passive"))
      (node (ref "T4") (pin "1") (pinfunction "Gate_1") (pintype "passive"))
    )
    (net (code "32") (name "/Relay_Ctrl5") (class "Default")
      (node (ref "DIO1") (pin "12") (pinfunction "12_12") (pintype "passive"))
      (node (ref "T5") (pin "1") (pinfunction "Gate_1") (pintype "passive"))
    )
    (net (code "33") (name "/Relay_Ctrl6") (class "Default")
      (node (ref "DIO1") (pin "11") (pinfunction "11_11") (pintype "passive"))
      (node (ref "T6") (pin "1") (pinfunction "Gate_1") (pintype "passive"))
    )
    (net (code "34") (name "/Relay_Ctrl7") (class "Default")
      (node (ref "DIO1") (pin "14") (pinfunction "14_14") (pintype "passive"))
      (node (ref "T7") (pin "1") (pinfunction "Gate_1") (pintype "passive"))
    )
    (net (code "35") (name "/Relay_Ctrl8") (class "Default")
      (node (ref "DIO1") (pin "13") (pinfunction "13_13") (pintype "passive"))
      (node (ref "T8") (pin "1") (pinfunction "Gate_1") (pintype "passive"))
    )
    (net (code "36") (name "/Relay_Ctrl9") (class "Default")
      (node (ref "DIO1") (pin "16") (pinfunction "16_16") (pintype "passive"))
      (node (ref "T9") (pin "1") (pinfunction "Gate_1") (pintype "passive"))
    )
    (net (code "37") (name "/Relay_Ctrl10") (class "Default")
      (node (ref "DIO1") (pin "15") (pinfunction "15_15") (pintype "passive"))
      (node (ref "T10") (pin "1") (pinfunction "Gate_1") (pintype "passive"))
    )
    (net (code "38") (name "/Relay_Ctrl11") (class "Default")
      (node (ref "DIO1") (pin "18") (pinfunction "18_18") (pintype "passive"))
      (node (ref "T11") (pin "1") (pinfunction "Gate_1") (pintype "passive"))
    )
    (net (code "39") (name "/Relay_Ctrl12") (class "Default")
      (node (ref "DIO1") (pin "17") (pinfunction "17_17") (pintype "passive"))
      (node (ref "T12") (pin "1") (pinfunction "Gate_1") (pintype "passive"))
    )
    (net (code "40") (name "/Relay_Ctrl13") (class "Default")
      (node (ref "DIO1") (pin "2") (pinfunction "2_2") (pintype "passive"))
      (node (ref "T13") (pin "1") (pinfunction "Gate_1") (pintype "passive"))
    )
    (net (code "41") (name "/Relay_Ctrl14") (class "Default")
      (node (ref "DIO1") (pin "4") (pinfunction "4_4") (pintype "passive"))
      (node (ref "T14") (pin "1") (pinfunction "Gate_1") (pintype "passive"))
    )
    (net (code "42") (name "/Relay_Ctrl15") (class "Default")
      (node (ref "DIO1") (pin "1") (pinfunction "1_1") (pintype "passive"))
      (node (ref "T15") (pin "1") (pinfunction "Gate_1") (pintype "passive"))
    )
    (net (code "43") (name "/Relay_Ctrl16") (class "Default")
      (node (ref "DIO1") (pin "5") (pinfunction "5_5") (pintype "passive"))
      (node (ref "T16") (pin "1") (pinfunction "Gate_1") (pintype "passive"))
    )
    (net (code "44") (name "/Relay_Ctrl17") (class "Default")
      (node (ref "DIO1") (pin "3") (pinfunction "3_3") (pintype "passive"))
      (node (ref "T17") (pin "1") (pinfunction "Gate_1") (pintype "passive"))
    )
    (net (code "45") (name "/Relay_Ctrl18") (class "Default")
      (node (ref "DIO1") (pin "6") (pinfunction "6_6") (pintype "passive"))
      (node (ref "T18") (pin "1") (pinfunction "Gate_1") (pintype "passive"))
    )
    (net (code "46") (name "/Relay_Ctrl19") (class "Default")
      (node (ref "DIO1") (pin "20") (pinfunction "20_20") (pintype "passive"))
      (node (ref "T19") (pin "1") (pinfunction "Gate_1") (pintype "passive"))
    )
    (net (code "47") (name "/Relay_Ctrl20") (class "Default")
      (node (ref "DIO1") (pin "19") (pinfunction "19_19") (pintype "passive"))
      (node (ref "T20") (pin "1") (pinfunction "Gate_1") (pintype "passive"))
    )
    (net (code "48") (name "/V_TRANS") (class "Default")
      (node (ref "K14") (pin "4") (pinfunction "4_4") (pintype "passive"))
      (node (ref "K18") (pin "4") (pinfunction "4_4") (pintype "passive"))
    )
    (net (code "49") (name "/V_TRANS2") (class "Default")
      (node (ref "K15") (pin "4") (pinfunction "4_4") (pintype "passive"))
      (node (ref "K17") (pin "2") (pinfunction "2_2") (pintype "passive"))
    )
    (net (code "50") (name "/WE_Follow") (class "Default")
      (node (ref "R19") (pin "1") (pinfunction "1_1") (pintype "passive"))
      (node (ref "U4") (pin "1") (pinfunction "Out_A_1") (pintype "passive"))
      (node (ref "U4") (pin "2") (pinfunction "-IN_A_2") (pintype "passive"))
    )
    (net (code "51") (name "AGND") (class "Default")
      (node (ref "C31") (pin "1") (pinfunction "1_1") (pintype "passive"))
      (node (ref "C32") (pin "1") (pinfunction "1_1") (pintype "passive"))
      (node (ref "C33") (pin "1") (pinfunction "1_1") (pintype "passive"))
      (node (ref "C34") (pin "1") (pinfunction "1_1") (pintype "passive"))
      (node (ref "C35") (pin "1") (pinfunction "1_1") (pintype "passive"))
      (node (ref "C36") (pin "1") (pinfunction "1_1") (pintype "passive"))
      (node (ref "C37") (pin "1") (pinfunction "1_1") (pintype "passive"))
      (node (ref "C38") (pin "2") (pinfunction "2_2") (pintype "passive"))
      (node (ref "C57") (pin "1") (pinfunction "1_1") (pintype "passive"))
      (node (ref "C58") (pin "2") (pinfunction "2_2") (pintype "passive"))
      (node (ref "C59") (pin "2") (pinfunction "2_2") (pintype "passive"))
      (node (ref "C63") (pin "2") (pinfunction "2_2") (pintype "passive"))
      (node (ref "C64") (pin "1") (pinfunction "1_1") (pintype "passive"))
      (node (ref "C65") (pin "1") (pinfunction "1_1") (pintype "passive"))
      (node (ref "C82") (pin "1") (pinfunction "1_1") (pintype "passive"))
      (node (ref "C83") (pin "2") (pinfunction "2_2") (pintype "passive"))
      (node (ref "C84") (pin "2") (pinfunction "2_2") (pintype "passive"))
      (node (ref "C85") (pin "1") (pinfunction "1_1") (pintype "passive"))
      (node (ref "C86") (pin "2") (pinfunction "2_2") (pintype "passive"))
      (node (ref "C87") (pin "1") (pinfunction "1_1") (pintype "passive"))
      (node (ref "C88") (pin "1") (pinfunction "1_1") (pintype "passive"))
      (node (ref "C89") (pin "2") (pinfunction "2_2") (pintype "passive"))
      (node (ref "CE") (pin "2") (pinfunction "Y_2") (pintype "passive"))
      (node (ref "D1") (pin "2") (pinfunction "K_2") (pintype "passive"))
      (node (ref "D2") (pin "1") (pinfunction "A_1") (pintype "passive"))
      (node (ref "PWR_15V") (pin "2") (pinfunction "2_2") (pintype "passive"))
      (node (ref "R20") (pin "1") (pinfunction "1_1") (pintype "passive"))
      (node (ref "RE") (pin "2") (pinfunction "Y_2") (pintype "passive"))
      (node (ref "SIG_IN") (pin "2") (pinfunction "Y_2") (pintype "passive"))
      (node (ref "SIG_OUT_A") (pin "2") (pinfunction "Y_2") (pintype "passive"))
      (node (ref "SIG_OUT_B") (pin "2") (pinfunction "Y_2") (pintype "passive"))
      (node (ref "T1") (pin "2") (pinfunction "Source_2") (pintype "passive"))
      (node (ref "T10") (pin "2") (pinfunction "Source_2") (pintype "passive"))
      (node (ref "T11") (pin "2") (pinfunction "Source_2") (pintype "passive"))
      (node (ref "T12") (pin "2") (pinfunction "Source_2") (pintype "passive"))
      (node (ref "T13") (pin "2") (pinfunction "Source_2") (pintype "passive"))
      (node (ref "T14") (pin "2") (pinfunction "Source_2") (pintype "passive"))
      (node (ref "T15") (pin "2") (pinfunction "Source_2") (pintype "passive"))
      (node (ref "T16") (pin "2") (pinfunction "Source_2") (pintype "passive"))
      (node (ref "T17") (pin "2") (pinfunction "Source_2") (pintype "passive"))
      (node (ref "T18") (pin "2") (pinfunction "Source_2") (pintype "passive"))
      (node (ref "T19") (pin "2") (pinfunction "Source_2") (pintype "passive"))
      (node (ref "T2") (pin "2") (pinfunction "Source_2") (pintype "passive"))
      (node (ref "T20") (pin "2") (pinfunction "Source_2") (pintype "passive"))
      (node (ref "T3") (pin "2") (pinfunction "Source_2") (pintype "passive"))
      (node (ref "T4") (pin "2") (pinfunction "Source_2") (pintype "passive"))
      (node (ref "T5") (pin "2") (pinfunction "Source_2") (pintype "passive"))
      (node (ref "T6") (pin "2") (pinfunction "Source_2") (pintype "passive"))
      (node (ref "T7") (pin "2") (pinfunction "Source_2") (pintype "passive"))
      (node (ref "T8") (pin "2") (pinfunction "Source_2") (pintype "passive"))
      (node (ref "T9") (pin "2") (pinfunction "Source_2") (pintype "passive"))
      (node (ref "U3") (pin "3") (pinfunction "+IN_A_3") (pintype "passive"))
      (node (ref "U4") (pin "5") (pinfunction "+IN_B_5") (pintype "passive"))
      (node (ref "WE") (pin "2") (pinfunction "Y_2") (pintype "passive"))
    )
    (net (code "52") (name "Net-(C70-Pad2)") (class "Default")
      (node (ref "C70") (pin "2") (pinfunction "2_2") (pintype "passive"))
      (node (ref "K1") (pin "4") (pinfunction "4_4") (pintype "passive"))
      (node (ref "R31") (pin "2") (pinfunction "2_2") (pintype "passive"))
    )
    (net (code "53") (name "Net-(C71-Pad2)") (class "Default")
      (node (ref "C71") (pin "2") (pinfunction "2_2") (pintype "passive"))
      (node (ref "K2") (pin "4") (pinfunction "4_4") (pintype "passive"))
      (node (ref "R32") (pin "2") (pinfunction "2_2") (pintype "passive"))
    )
    (net (code "54") (name "Net-(C72-Pad2)") (class "Default")
      (node (ref "C72") (pin "2") (pinfunction "2_2") (pintype "passive"))
      (node (ref "K3") (pin "4") (pinfunction "4_4") (pintype "passive"))
      (node (ref "R33") (pin "2") (pinfunction "2_2") (pintype "passive"))
    )
    (net (code "55") (name "Net-(C73-Pad2)") (class "Default")
      (node (ref "C73") (pin "2") (pinfunction "2_2") (pintype "passive"))
      (node (ref "K4") (pin "4") (pinfunction "4_4") (pintype "passive"))
      (node (ref "R34") (pin "2") (pinfunction "2_2") (pintype "passive"))
    )
    (net (code "56") (name "Net-(C74-Pad2)") (class "Default")
      (node (ref "C74") (pin "2") (pinfunction "2_2") (pintype "passive"))
      (node (ref "K5") (pin "4") (pinfunction "4_4") (pintype "passive"))
      (node (ref "R35") (pin "2") (pinfunction "2_2") (pintype "passive"))
    )
    (net (code "57") (name "Net-(C75-Pad2)") (class "Default")
      (node (ref "C75") (pin "2") (pinfunction "2_2") (pintype "passive"))
      (node (ref "K6") (pin "4") (pinfunction "4_4") (pintype "passive"))
      (node (ref "R36") (pin "2") (pinfunction "2_2") (pintype "passive"))
    )
    (net (code "58") (name "Net-(C76-Pad2)") (class "Default")
      (node (ref "C76") (pin "2") (pinfunction "2_2") (pintype "passive"))
      (node (ref "K7") (pin "4") (pinfunction "4_4") (pintype "passive"))
      (node (ref "R37") (pin "2") (pinfunction "2_2") (pintype "passive"))
    )
    (net (code "59") (name "Net-(C77-Pad2)") (class "Default")
      (node (ref "C77") (pin "2") (pinfunction "2_2") (pintype "passive"))
      (node (ref "K8") (pin "4") (pinfunction "4_4") (pintype "passive"))
      (node (ref "R38") (pin "2") (pinfunction "2_2") (pintype "passive"))
    )
    (net (code "60") (name "Net-(C78-Pad2)") (class "Default")
      (node (ref "C78") (pin "2") (pinfunction "2_2") (pintype "passive"))
      (node (ref "K9") (pin "4") (pinfunction "4_4") (pintype "passive"))
      (node (ref "R39") (pin "2") (pinfunction "2_2") (pintype "passive"))
    )
    (net (code "61") (name "Net-(C79-Pad2)") (class "Default")
      (node (ref "C79") (pin "2") (pinfunction "2_2") (pintype "passive"))
      (node (ref "K10") (pin "4") (pinfunction "4_4") (pintype "passive"))
      (node (ref "R40") (pin "2") (pinfunction "2_2") (pintype "passive"))
    )
    (net (code "62") (name "Net-(D1-A)") (class "Default")
      (node (ref "D1") (pin "1") (pinfunction "A_1") (pintype "passive"))
      (node (ref "R1") (pin "2") (pinfunction "2_2") (pintype "passive"))
    )
    (net (code "63") (name "Net-(D2-K)") (class "Default")
      (node (ref "D2") (pin "2") (pinfunction "K_2") (pintype "passive"))
      (node (ref "R2") (pin "1") (pinfunction "1_1") (pintype "passive"))
    )
    (net (code "64") (name "Net-(K1-Pad3)") (class "Default")
      (node (ref "K1") (pin "3") (pinfunction "3_3") (pintype "passive"))
      (node (ref "K1") (pin "6") (pinfunction "6_6") (pintype "passive"))
    )
    (net (code "65") (name "Net-(K2-Pad3)") (class "Default")
      (node (ref "K2") (pin "3") (pinfunction "3_3") (pintype "passive"))
      (node (ref "K2") (pin "6") (pinfunction "6_6") (pintype "passive"))
    )
    (net (code "66") (name "Net-(K3-Pad3)") (class "Default")
      (node (ref "K3") (pin "3") (pinfunction "3_3") (pintype "passive"))
      (node (ref "K3") (pin "6") (pinfunction "6_6") (pintype "passive"))
    )
    (net (code "67") (name "Net-(K4-Pad3)") (class "Default")
      (node (ref "K4") (pin "3") (pinfunction "3_3") (pintype "passive"))
      (node (ref "K4") (pin "6") (pinfunction "6_6") (pintype "passive"))
    )
    (net (code "68") (name "Net-(K5-Pad3)") (class "Default")
      (node (ref "K5") (pin "3") (pinfunction "3_3") (pintype "passive"))
      (node (ref "K5") (pin "6") (pinfunction "6_6") (pintype "passive"))
    )
    (net (code "69") (name "Net-(K6-Pad3)") (class "Default")
      (node (ref "K6") (pin "3") (pinfunction "3_3") (pintype "passive"))
      (node (ref "K6") (pin "6") (pinfunction "6_6") (pintype "passive"))
    )
    (net (code "70") (name "Net-(K7-Pad3)") (class "Default")
      (node (ref "K7") (pin "3") (pinfunction "3_3") (pintype "passive"))
      (node (ref "K7") (pin "6") (pinfunction "6_6") (pintype "passive"))
    )
    (net (code "71") (name "Net-(K8-Pad3)") (class "Default")
      (node (ref "K8") (pin "3") (pinfunction "3_3") (pintype "passive"))
      (node (ref "K8") (pin "6") (pinfunction "6_6") (pintype "passive"))
    )
    (net (code "72") (name "Net-(K9-Pad3)") (class "Default")
      (node (ref "K9") (pin "3") (pinfunction "3_3") (pintype "passive"))
      (node (ref "K9") (pin "6") (pinfunction "6_6") (pintype "passive"))
    )
    (net (code "73") (name "Net-(K10-Pad3)") (class "Default")
      (node (ref "K10") (pin "3") (pinfunction "3_3") (pintype "passive"))
      (node (ref "K10") (pin "6") (pinfunction "6_6") (pintype "passive"))
    )
    (net (code "74") (name "Net-(K11-Pad3)") (class "Default")
      (node (ref "K11") (pin "3") (pinfunction "3_3") (pintype "passive"))
      (node (ref "K11") (pin "6") (pinfunction "6_6") (pintype "passive"))
    )
    (net (code "75") (name "Net-(K11-Pad5)") (class "Default")
      (node (ref "K11") (pin "5") (pinfunction "5_5") (pintype "passive"))
      (node (ref "K12") (pin "2") (pinfunction "2_2") (pintype "passive"))
      (node (ref "K12") (pin "4") (pinfunction "4_4") (pintype "passive"))
      (node (ref "K13") (pin "2") (pinfunction "2_2") (pintype "passive"))
    )
    (net (code "76") (name "Net-(K12-Pad3)") (class "Default")
      (node (ref "K12") (pin "3") (pinfunction "3_3") (pintype "passive"))
      (node (ref "K12") (pin "6") (pinfunction "6_6") (pintype "passive"))
    )
    (net (code "77") (name "Net-(K12-Pad5)") (class "Default")
      (node (ref "K12") (pin "5") (pinfunction "5_5") (pintype "passive"))
      (node (ref "R26") (pin "1") (pinfunction "1_1") (pintype "passive"))
    )
    (net (code "78") (name "Net-(K12-Pad7)") (class "Default")
      (node (ref "K12") (pin "7") (pinfunction "7_7") (pintype "passive"))
      (node (ref "R25") (pin "1") (pinfunction "1_1") (pintype "passive"))
    )
    (net (code "79") (name "Net-(K13-Pad3)") (class "Default")
      (node (ref "K13") (pin "3") (pinfunction "3_3") (pintype "passive"))
      (node (ref "K13") (pin "6") (pinfunction "6_6") (pintype "passive"))
    )
    (net (code "80") (name "Net-(K14-Pad2)") (class "Default")
      (node (ref "K14") (pin "2") (pinfunction "2_2") (pintype "passive"))
      (node (ref "K15") (pin "5") (pinfunction "5_5") (pintype "passive"))
      (node (ref "K15") (pin "7") (pinfunction "7_7") (pintype "passive"))
    )
    (net (code "81") (name "Net-(K14-Pad3)") (class "Default")
      (node (ref "K14") (pin "3") (pinfunction "3_3") (pintype "passive"))
      (node (ref "K14") (pin "6") (pinfunction "6_6") (pintype "passive"))
    )
    (net (code "82") (name "Net-(K15-Pad3)") (class "Default")
      (node (ref "K15") (pin "3") (pinfunction "3_3") (pintype "passive"))
      (node (ref "K15") (pin "6") (pinfunction "6_6") (pintype "passive"))
    )
    (net (code "83") (name "Net-(K16-Pad3)") (class "Default")
      (node (ref "K16") (pin "3") (pinfunction "3_3") (pintype "passive"))
      (node (ref "K16") (pin "6") (pinfunction "6_6") (pintype "passive"))
    )
    (net (code "84") (name "Net-(K17-Pad3)") (class "Default")
      (node (ref "K17") (pin "3") (pinfunction "3_3") (pintype "passive"))
      (node (ref "K17") (pin "6") (pinfunction "6_6") (pintype "passive"))
    )
    (net (code "85") (name "Net-(K17-Pad4)") (class "Default")
      (node (ref "K17") (pin "4") (pinfunction "4_4") (pintype "passive"))
      (node (ref "K18") (pin "5") (pinfunction "5_5") (pintype "passive"))
      (node (ref "K18") (pin "7") (pinfunction "7_7") (pintype "passive"))
    )
    (net (code "86") (name "Net-(K18-Pad3)") (class "Default")
      (node (ref "K18") (pin "3") (pinfunction "3_3") (pintype "passive"))
      (node (ref "K18") (pin "6") (pinfunction "6_6") (pintype "passive"))
    )
    (net (code "87") (name "Net-(K19-Pad3)") (class "Default")
      (node (ref "K19") (pin "3") (pinfunction "3_3") (pintype "passive"))
      (node (ref "K19") (pin "6") (pinfunction "6_6") (pintype "passive"))
    )
    (net (code "88") (name "Net-(K20-Pad3)") (class "Default")
      (node (ref "K20") (pin "3") (pinfunction "3_3") (pintype "passive"))
      (node (ref "K20") (pin "6") (pinfunction "6_6") (pintype "passive"))
    )
    (net (code "89") (name "Net-(SIG_IN-X)") (class "Default")
      (node (ref "R24") (pin "1") (pinfunction "1_1") (pintype "passive"))
      (node (ref "SIG_IN") (pin "1") (pinfunction "X_1") (pintype "passive"))
    )
    (net (code "90") (name "Net-(SIG_OUT_A-X)") (class "Default")
      (node (ref "K19") (pin "2") (pinfunction "2_2") (pintype "passive"))
      (node (ref "K19") (pin "4") (pinfunction "4_4") (pintype "passive"))
      (node (ref "SIG_OUT_A") (pin "1") (pinfunction "X_1") (pintype "passive"))
    )
    (net (code "91") (name "Net-(SIG_OUT_B-X)") (class "Default")
      (node (ref "K20") (pin "2") (pinfunction "2_2") (pintype "passive"))
      (node (ref "K20") (pin "4") (pinfunction "4_4") (pintype "passive"))
      (node (ref "SIG_OUT_B") (pin "1") (pinfunction "X_1") (pintype "passive"))
    )
    (net (code "92") (name "Net-(U2-BW)") (class "Default")
      (node (ref "R27") (pin "2") (pinfunction "2_2") (pintype "passive"))
      (node (ref "U2") (pin "1") (pinfunction "BW_1") (pintype "passive"))
    )
    (net (code "93") (name "Net-(U2-Vin)") (class "Default")
      (node (ref "K15") (pin "2") (pinfunction "2_2") (pintype "passive"))
      (node (ref "U2") (pin "2") (pinfunction "Vin_2") (pintype "passive"))
    )
    (net (code "94") (name "Net-(U2-Vout)") (class "Default")
      (node (ref "R3") (pin "1") (pinfunction "1_1") (pintype "passive"))
      (node (ref "U2") (pin "4") (pinfunction "Vout_4") (pintype "passive"))
    )
    (net (code "95") (name "Net-(U3--IN_A)") (class "Default")
      (node (ref "R24") (pin "2") (pinfunction "2_2") (pintype "passive"))
      (node (ref "R25") (pin "2") (pinfunction "2_2") (pintype "passive"))
      (node (ref "R26") (pin "2") (pinfunction "2_2") (pintype "passive"))
      (node (ref "U3") (pin "2") (pinfunction "-IN_A_2") (pintype "passive"))
    )
    (net (code "96") (name "Net-(U3-Out_A)") (class "Default")
      (node (ref "K11") (pin "4") (pinfunction "4_4") (pintype "passive"))
      (node (ref "K14") (pin "5") (pinfunction "5_5") (pintype "passive"))
      (node (ref "K14") (pin "7") (pinfunction "7_7") (pintype "passive"))
      (node (ref "U3") (pin "1") (pinfunction "Out_A_1") (pintype "passive"))
    )
    (net (code "97") (name "Net-(U4-+IN_A)") (class "Default")
      (node (ref "K16") (pin "4") (pinfunction "4_4") (pintype "passive"))
      (node (ref "U4") (pin "3") (pinfunction "+IN_A_3") (pintype "passive"))
    )
    (net (code "98") (name "Net-(U4-Out_B)") (class "Default")
      (node (ref "K17") (pin "5") (pinfunction "5_5") (pintype "passive"))
      (node (ref "K17") (pin "7") (pinfunction "7_7") (pintype "passive"))
      (node (ref "U4") (pin "7") (pinfunction "Out_B_7") (pintype "passive"))
    )
    (net (code "99") (name "Net-(U5-+IN_A)") (class "Default")
      (node (ref "R19") (pin "2") (pinfunction "2_2") (pintype "passive"))
      (node (ref "R20") (pin "2") (pinfunction "2_2") (pintype "passive"))
      (node (ref "U5") (pin "3") (pinfunction "+IN_A_3") (pintype "passive"))
    )
    (net (code "100") (name "Net-(U5--IN_A)") (class "Default")
      (node (ref "R21") (pin "1") (pinfunction "1_1") (pintype "passive"))
      (node (ref "R22") (pin "2") (pinfunction "2_2") (pintype "passive"))
      (node (ref "U5") (pin "2") (pinfunction "-IN_A_2") (pintype "passive"))
    )
    (net (code "101") (name "Net-(U5--IN_B)") (class "Default")
      (node (ref "K20") (pin "7") (pinfunction "7_7") (pintype "passive"))
      (node (ref "U5") (pin "6") (pinfunction "-IN_B_6") (pintype "passive"))
      (node (ref "U5") (pin "7") (pinfunction "Out_B_7") (pintype "passive"))
    )
    (net (code "102") (name "Net-(U5-Out_A)") (class "Default")
      (node (ref "K20") (pin "5") (pinfunction "5_5") (pintype "passive"))
      (node (ref "R22") (pin "1") (pinfunction "1_1") (pintype "passive"))
      (node (ref "U5") (pin "1") (pinfunction "Out_A_1") (pintype "passive"))
    )
    (net (code "103") (name "Net-(U22-BW)") (class "Default")
      (node (ref "R18") (pin "2") (pinfunction "2_2") (pintype "passive"))
      (node (ref "U22") (pin "1") (pinfunction "BW_1") (pintype "passive"))
    )
    (net (code "104") (name "Net-(U22-Vin)") (class "Default")
      (node (ref "K18") (pin "2") (pinfunction "2_2") (pintype "passive"))
      (node (ref "U22") (pin "2") (pinfunction "Vin_2") (pintype "passive"))
    )
    (net (code "105") (name "Net-(U22-Vout)") (class "Default")
      (node (ref "R30") (pin "1") (pinfunction "1_1") (pintype "passive"))
      (node (ref "U22") (pin "4") (pinfunction "Vout_4") (pintype "passive"))
    )
    (net (code "106") (name "Net-(WE-X)") (class "Default")
      (node (ref "K16") (pin "5") (pinfunction "5_5") (pintype "passive"))
      (node (ref "K16") (pin "7") (pinfunction "7_7") (pintype "passive"))
      (node (ref "WE") (pin "1") (pinfunction "X_1") (pintype "passive"))
    )
    (net (code "107") (name "unconnected-(K1-Pad2)") (class "Default")
      (node (ref "K1") (pin "2") (pinfunction "2_2") (pintype "passive"))
    )
    (net (code "108") (name "unconnected-(K1-Pad7)") (class "Default")
      (node (ref "K1") (pin "7") (pinfunction "7_7") (pintype "passive"))
    )
    (net (code "109") (name "unconnected-(K2-Pad2)") (class "Default")
      (node (ref "K2") (pin "2") (pinfunction "2_2") (pintype "passive"))
    )
    (net (code "110") (name "unconnected-(K2-Pad7)") (class "Default")
      (node (ref "K2") (pin "7") (pinfunction "7_7") (pintype "passive"))
    )
    (net (code "111") (name "unconnected-(K3-Pad2)") (class "Default")
      (node (ref "K3") (pin "2") (pinfunction "2_2") (pintype "passive"))
    )
    (net (code "112") (name "unconnected-(K3-Pad7)") (class "Default")
      (node (ref "K3") (pin "7") (pinfunction "7_7") (pintype "passive"))
    )
    (net (code "113") (name "unconnected-(K4-Pad2)") (class "Default")
      (node (ref "K4") (pin "2") (pinfunction "2_2") (pintype "passive"))
    )
    (net (code "114") (name "unconnected-(K4-Pad7)") (class "Default")
      (node (ref "K4") (pin "7") (pinfunction "7_7") (pintype "passive"))
    )
    (net (code "115") (name "unconnected-(K5-Pad2)") (class "Default")
      (node (ref "K5") (pin "2") (pinfunction "2_2") (pintype "passive"))
    )
    (net (code "116") (name "unconnected-(K5-Pad7)") (class "Default")
      (node (ref "K5") (pin "7") (pinfunction "7_7") (pintype "passive"))
    )
    (net (code "117") (name "unconnected-(K6-Pad2)") (class "Default")
      (node (ref "K6") (pin "2") (pinfunction "2_2") (pintype "passive"))
    )
    (net (code "118") (name "unconnected-(K6-Pad7)") (class "Default")
      (node (ref "K6") (pin "7") (pinfunction "7_7") (pintype "passive"))
    )
    (net (code "119") (name "unconnected-(K7-Pad2)") (class "Default")
      (node (ref "K7") (pin "2") (pinfunction "2_2") (pintype "passive"))
    )
    (net (code "120") (name "unconnected-(K7-Pad7)") (class "Default")
      (node (ref "K7") (pin "7") (pinfunction "7_7") (pintype "passive"))
    )
    (net (code "121") (name "unconnected-(K8-Pad2)") (class "Default")
      (node (ref "K8") (pin "2") (pinfunction "2_2") (pintype "passive"))
    )
    (net (code "122") (name "unconnected-(K8-Pad7)") (class "Default")
      (node (ref "K8") (pin "7") (pinfunction "7_7") (pintype "passive"))
    )
    (net (code "123") (name "unconnected-(K9-Pad2)") (class "Default")
      (node (ref "K9") (pin "2") (pinfunction "2_2") (pintype "passive"))
    )
    (net (code "124") (name "unconnected-(K9-Pad7)") (class "Default")
      (node (ref "K9") (pin "7") (pinfunction "7_7") (pintype "passive"))
    )
    (net (code "125") (name "unconnected-(K10-Pad2)") (class "Default")
      (node (ref "K10") (pin "2") (pinfunction "2_2") (pintype "passive"))
    )
    (net (code "126") (name "unconnected-(K10-Pad7)") (class "Default")
      (node (ref "K10") (pin "7") (pinfunction "7_7") (pintype "passive"))
    )
    (net (code "127") (name "unconnected-(K11-Pad2)") (class "Default")
      (node (ref "K11") (pin "2") (pinfunction "2_2") (pintype "passive"))
    )
    (net (code "128") (name "unconnected-(K11-Pad7)") (class "Default")
      (node (ref "K11") (pin "7") (pinfunction "7_7") (pintype "passive"))
    )
    (net (code "129") (name "unconnected-(K13-Pad4)") (class "Default")
      (node (ref "K13") (pin "4") (pinfunction "4_4") (pintype "passive"))
    )
    (net (code "130") (name "unconnected-(K13-Pad5)") (class "Default")
      (node (ref "K13") (pin "5") (pinfunction "5_5") (pintype "passive"))
    )
  )
)
